# LED_Driver.net
KiCad netlist of a schematic drawn in Altium Designer
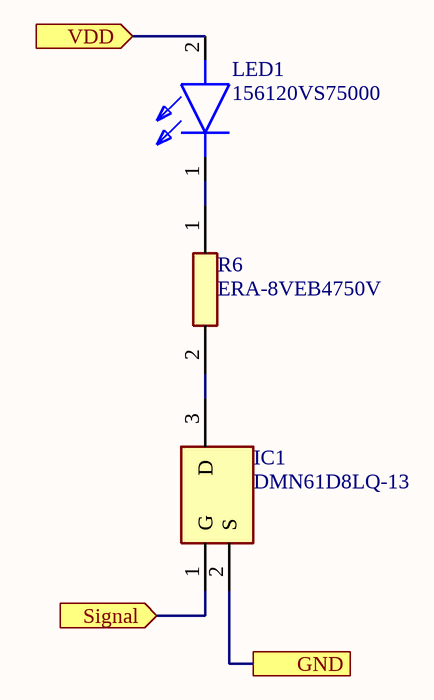
[diagram p0: LED_Driver.SchDoc]

(export (version "E")
  (design (tool "Eeschema 10.0.6"))
  (components
    (comp (ref "IC1")
      (value "DMN61D8LQ-13")
      (footprint "SamacSys:SOT96P240X110-3N")
      (description "Integrated Circuit")
      (fields (field (name "MOUSER PART NUMBER") "621-DMN61D8LQ-13"))
      (libsource (lib "SamacSys") (part "DMN61D8LQ-13"))
    )
    (comp (ref "LED1")
      (value "156120VS75000")
      (footprint "SamacSys:156120VS75000")
      (description "LED")
      (fields (field (name "MOUSER PART NUMBER") "710-156120VS75000"))
      (libsource (lib "SamacSys") (part "156120VS75000"))
    )
    (comp (ref "R6")
      (value "ERA-8VEB4750V")
      (footprint "SamacSys:ERA8KEB1004V")
      (description "Resistor")
      (fields (field (name "MOUSER PART NUMBER") "667-ERA-8VEB4750V"))
      (libsource (lib "*") (part "ERA-8VEB4750V"))
    )
  )
  (nets
    (net (code "1") (name "/GND") (class "Default")
      (node (ref "IC1") (pin "2") (pinfunction "S_2") (pintype "passive"))
    )
    (net (code "2") (name "/Signal") (class "Default")
      (node (ref "IC1") (pin "1") (pinfunction "G_1") (pintype "passive"))
    )
    (net (code "3") (name "/VDD") (class "Default")
      (node (ref "LED1") (pin "2") (pinfunction "A_2") (pintype "passive"))
    )
    (net (code "4") (name "Net-(IC1-D)") (class "Default")
      (node (ref "IC1") (pin "3") (pinfunction "D_3") (pintype "passive"))
      (node (ref "R6") (pin "2") (pinfunction "2_2") (pintype "passive"))
    )
    (net (code "5") (name "Net-(LED1-K)") (class "Default")
      (node (ref "LED1") (pin "1") (pinfunction "K_1") (pintype "passive"))
      (node (ref "R6") (pin "1") (pinfunction "1_1") (pintype "passive"))
    )
  )
)
